# power_supply.net
KiCad netlist of a schematic drawn in Altium Designer
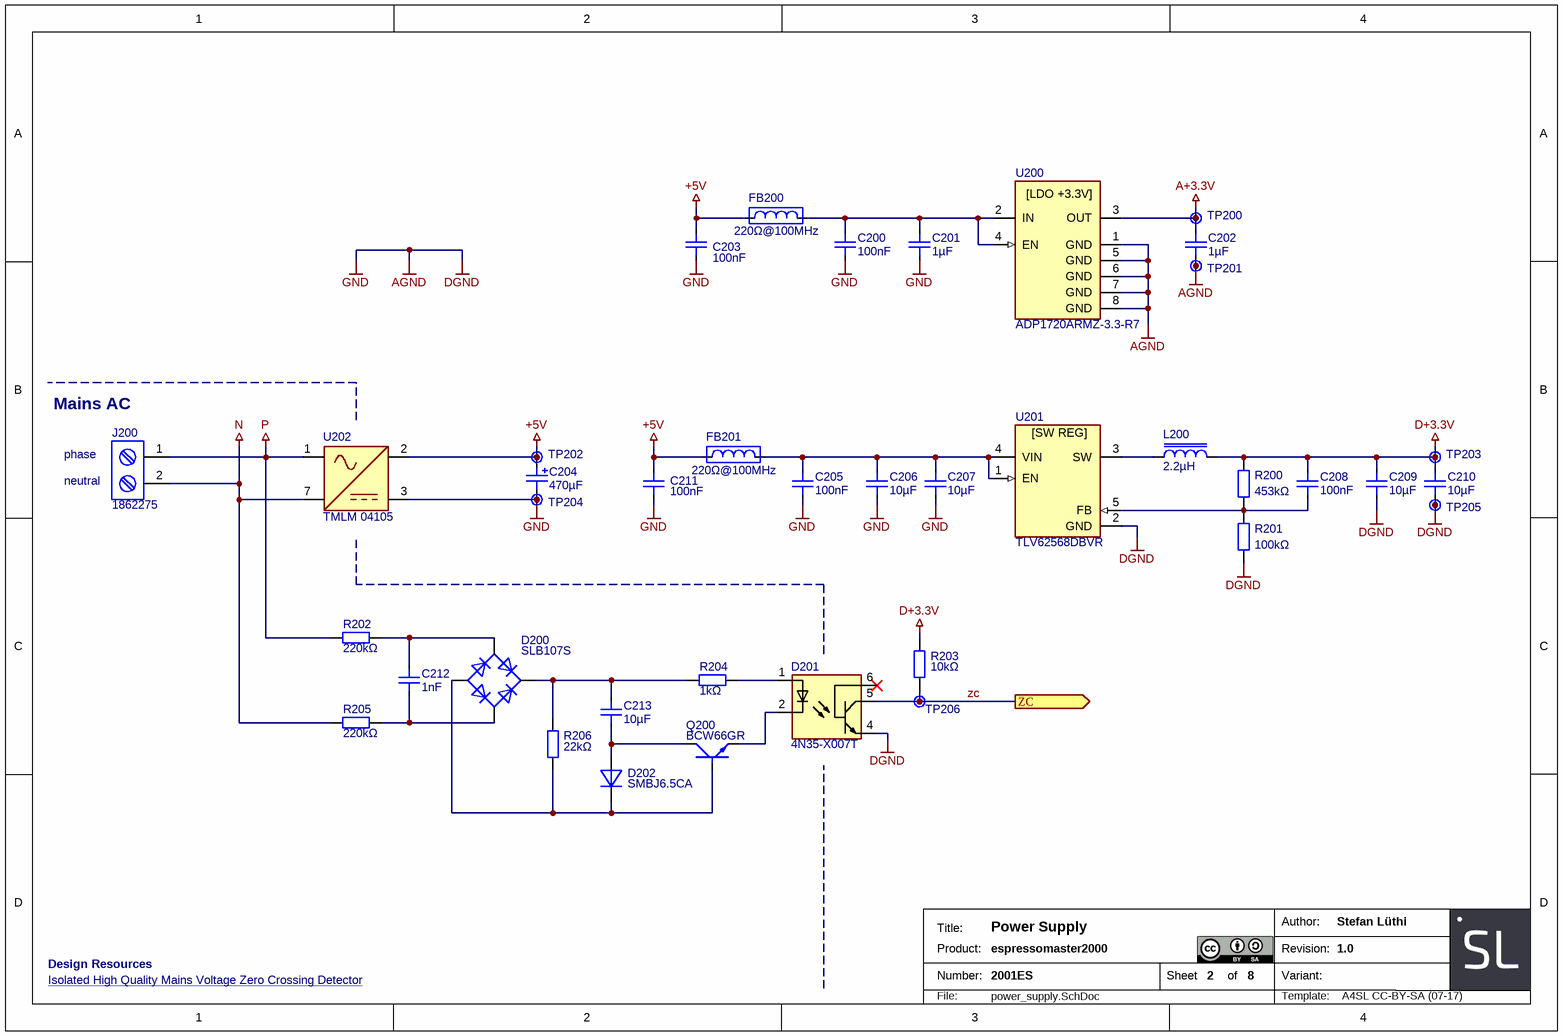
[diagram p0: power_supply.SchDoc]

(export (version "E")
  (design (tool "Eeschema 10.0.6"))
  (components
    (comp (ref "C200")
      (value "100nF")
      (footprint "SMD0603CAP")
      (description "Ceramic Capacitor")
      (libsource (lib "SL-Library") (part "Capacitor Ceramic"))
    )
    (comp (ref "C201")
      (value "1µF")
      (footprint "SMD0603CAP")
      (description "Ceramic Capacitor")
      (libsource (lib "SL-Library") (part "Capacitor Ceramic"))
    )
    (comp (ref "C202")
      (value "1µF")
      (footprint "SMD0603CAP")
      (description "Ceramic Capacitor")
      (libsource (lib "SL-Library") (part "Capacitor Ceramic"))
    )
    (comp (ref "C203")
      (value "100nF")
      (footprint "SMD0603CAP")
      (description "Ceramic Capacitor")
      (libsource (lib "SL-Library") (part "Capacitor Ceramic"))
    )
    (comp (ref "C204")
      (value "470µF")
      (footprint "CAP-12.5-20-5")
      (description "Elektrolytic Capacitor")
      (libsource (lib "SL-Library") (part "Capacitor Electrolytic"))
    )
    (comp (ref "C205")
      (value "100nF")
      (footprint "SMD0603CAP")
      (description "Ceramic Capacitor")
      (libsource (lib "SL-Library") (part "Capacitor Ceramic"))
    )
    (comp (ref "C206")
      (value "10µF")
      (footprint "SMD1206CAP")
      (description "Ceramic Capacitor")
      (libsource (lib "SL-Library") (part "Capacitor Ceramic"))
    )
    (comp (ref "C207")
      (value "10µF")
      (footprint "SMD1206CAP")
      (description "Ceramic Capacitor")
      (libsource (lib "SL-Library") (part "Capacitor Ceramic"))
    )
    (comp (ref "C208")
      (value "100nF")
      (footprint "SMD0603CAP")
      (description "Ceramic Capacitor")
      (libsource (lib "SL-Library") (part "Capacitor Ceramic"))
    )
    (comp (ref "C209")
      (value "10µF")
      (footprint "SMD1206CAP")
      (description "Ceramic Capacitor")
      (libsource (lib "SL-Library") (part "Capacitor Ceramic"))
    )
    (comp (ref "C210")
      (value "10µF")
      (footprint "SMD1206CAP")
      (description "Ceramic Capacitor")
      (libsource (lib "SL-Library") (part "Capacitor Ceramic"))
    )
    (comp (ref "C211")
      (value "100nF")
      (footprint "SMD0603CAP")
      (description "Ceramic Capacitor")
      (libsource (lib "SL-Library") (part "Capacitor Ceramic"))
    )
    (comp (ref "C212")
      (value "1nF")
      (footprint "SMD0603CAP")
      (description "Ceramic Capacitor")
      (libsource (lib "SL-Library") (part "Capacitor Ceramic"))
    )
    (comp (ref "C213")
      (value "10µF")
      (footprint "SMD1206CAP")
      (description "Ceramic Capacitor")
      (libsource (lib "SL-Library") (part "Capacitor Ceramic"))
    )
    (comp (ref "D200")
      (value "SLB107S")
      (footprint "SLDBS-4")
      (description "Full Bridge Rectifier")
      (libsource (lib "SL-Library") (part "Rectifier"))
    )
    (comp (ref "D201")
      (value "4N35-X007T")
      (footprint "SMT6-LB")
      (description "Optocoupler")
      (libsource (lib "SL-Library") (part "4N35-X"))
    )
    (comp (ref "D202")
      (value "SMBJ6.5CA")
      (footprint "DO-214AA")
      (description "Diode")
      (libsource (lib "SL-Library") (part "Diode"))
    )
    (comp (ref "FB200")
      (value "220Ω@100MHz")
      (footprint "SMD0603RES")
      (description "Ferrite Bead")
      (libsource (lib "SL-Library") (part "Ferrite Bead"))
    )
    (comp (ref "FB201")
      (value "220Ω@100MHz")
      (footprint "SMD0603RES")
      (description "Ferrite Bead")
      (libsource (lib "SL-Library") (part "Ferrite Bead"))
    )
    (comp (ref "J200")
      (value "1862275")
      (footprint "1862275")
      (description "Screw Terminal, 2 Position, 5mm Spacing")
      (libsource (lib "SL-Library") (part "1862275"))
    )
    (comp (ref "L200")
      (value "2.2µH")
      (footprint "WE4040")
      (description "Inductor")
      (libsource (lib "SL-Library") (part "Inductor"))
    )
    (comp (ref "Q200")
      (value "BCW66GR")
      (footprint "SOT-23")
      (description "Bipolar transistor NPN")
      (libsource (lib "SL-Library") (part "Transistor NPN"))
    )
    (comp (ref "R200")
      (value "453kΩ")
      (footprint "SMD0603RES")
      (description "Resistor")
      (libsource (lib "SL-Library") (part "Resistor"))
    )
    (comp (ref "R201")
      (value "100kΩ")
      (footprint "SMD0603RES")
      (description "Resistor")
      (libsource (lib "SL-Library") (part "Resistor"))
    )
    (comp (ref "R202")
      (value "220kΩ")
      (footprint "SMD2010RES")
      (description "Resistor")
      (libsource (lib "") (part "Resistor_1"))
    )
    (comp (ref "R203")
      (value "10kΩ")
      (footprint "SMD0603RES")
      (description "Resistor")
      (libsource (lib "SL-Library") (part "Resistor"))
    )
    (comp (ref "R204")
      (value "1kΩ")
      (footprint "SMD0603RES")
      (description "Resistor")
      (libsource (lib "") (part "Resistor_1"))
    )
    (comp (ref "R205")
      (value "220kΩ")
      (footprint "SMD2010RES")
      (description "Resistor")
      (libsource (lib "") (part "Resistor_1"))
    )
    (comp (ref "R206")
      (value "22kΩ")
      (footprint "SMD0603RES")
      (description "Resistor")
      (libsource (lib "SL-Library") (part "Resistor"))
    )
    (comp (ref "TP200")
      (value "Testpoint")
      (footprint "TP")
      (libsource (lib "SL-Library") (part "Testpoint"))
    )
    (comp (ref "TP201")
      (value "Testpoint")
      (footprint "TP")
      (libsource (lib "SL-Library") (part "Testpoint"))
    )
    (comp (ref "TP202")
      (value "Testpoint")
      (footprint "TP")
      (libsource (lib "SL-Library") (part "Testpoint"))
    )
    (comp (ref "TP203")
      (value "Testpoint")
      (footprint "TP")
      (libsource (lib "SL-Library") (part "Testpoint"))
    )
    (comp (ref "TP204")
      (value "Testpoint")
      (footprint "TP")
      (libsource (lib "SL-Library") (part "Testpoint"))
    )
    (comp (ref "TP205")
      (value "Testpoint")
      (footprint "TP")
      (libsource (lib "SL-Library") (part "Testpoint"))
    )
    (comp (ref "TP206")
      (value "Testpoint")
      (footprint "TP")
      (libsource (lib "SL-Library") (part "Testpoint"))
    )
    (comp (ref "U200")
      (value "ADP1720ARMZ-3.3-R7")
      (footprint "MSOP8")
      (description "LDO 3.3V Output")
      (libsource (lib "SL-Library") (part "ADP1720ARMZ-3.3-R7"))
    )
    (comp (ref "U201")
      (value "TLV62568DBVR")
      (footprint "SOT-23-5")
      (description "Step-Down Regulator")
      (libsource (lib "SL-Library") (part "TLV62568DBVR"))
    )
    (comp (ref "U202")
      (value "TMLM 04105")
      (footprint "TMLM04")
      (description "AC/DC Converter (100VAC - 240VAC to 5VDC)")
      (libsource (lib "SL-Library") (part "TMLM 04"))
    )
  )
  (nets
    (net (code "1") (name "+5V") (class "Default")
      (node (ref "C203") (pin "1") (pinfunction "1_1") (pintype "passive"))
      (node (ref "C204") (pin "P") (pinfunction "P_P") (pintype "passive"))
      (node (ref "C211") (pin "1") (pinfunction "1_1") (pintype "passive"))
      (node (ref "FB200") (pin "1") (pinfunction "1_1") (pintype "passive"))
      (node (ref "FB201") (pin "1") (pinfunction "1_1") (pintype "passive"))
      (node (ref "TP202") (pin "1") (pinfunction "1_1") (pintype "passive"))
      (node (ref "U202") (pin "2") (pinfunction "V+_2") (pintype "power_in"))
    )
    (net (code "2") (name "/zc") (class "Default")
      (node (ref "D201") (pin "5") (pinfunction "5_5") (pintype "passive"))
      (node (ref "R203") (pin "1") (pinfunction "1_1") (pintype "passive"))
      (node (ref "TP206") (pin "1") (pinfunction "1_1") (pintype "passive"))
    )
    (net (code "3") (name "A+3.3V") (class "Default")
      (node (ref "C202") (pin "1") (pinfunction "1_1") (pintype "passive"))
      (node (ref "TP200") (pin "1") (pinfunction "1_1") (pintype "passive"))
      (node (ref "U200") (pin "3") (pinfunction "OUT_3") (pintype "power_in"))
    )
    (net (code "4") (name "AGND") (class "Default")
      (node (ref "C200") (pin "2") (pinfunction "2_2") (pintype "passive"))
      (node (ref "C201") (pin "2") (pinfunction "2_2") (pintype "passive"))
      (node (ref "C202") (pin "2") (pinfunction "2_2") (pintype "passive"))
      (node (ref "C203") (pin "2") (pinfunction "2_2") (pintype "passive"))
      (node (ref "C204") (pin "M") (pinfunction "M_M") (pintype "passive"))
      (node (ref "C205") (pin "2") (pinfunction "2_2") (pintype "passive"))
      (node (ref "C206") (pin "2") (pinfunction "2_2") (pintype "passive"))
      (node (ref "C207") (pin "2") (pinfunction "2_2") (pintype "passive"))
      (node (ref "C209") (pin "2") (pinfunction "2_2") (pintype "passive"))
      (node (ref "C210") (pin "2") (pinfunction "2_2") (pintype "passive"))
      (node (ref "C211") (pin "2") (pinfunction "2_2") (pintype "passive"))
      (node (ref "D201") (pin "4") (pinfunction "4_4") (pintype "passive"))
      (node (ref "R201") (pin "1") (pinfunction "1_1") (pintype "passive"))
      (node (ref "TP201") (pin "1") (pinfunction "1_1") (pintype "passive"))
      (node (ref "TP204") (pin "1") (pinfunction "1_1") (pintype "passive"))
      (node (ref "TP205") (pin "1") (pinfunction "1_1") (pintype "passive"))
      (node (ref "U200") (pin "1") (pinfunction "GND_1") (pintype "power_in"))
      (node (ref "U200") (pin "5") (pinfunction "GND_5") (pintype "power_in"))
      (node (ref "U200") (pin "6") (pinfunction "GND_6") (pintype "power_in"))
      (node (ref "U200") (pin "7") (pinfunction "GND_7") (pintype "power_in"))
      (node (ref "U200") (pin "8") (pinfunction "GND_8") (pintype "power_in"))
      (node (ref "U201") (pin "2") (pinfunction "GND_2") (pintype "power_in"))
      (node (ref "U202") (pin "3") (pinfunction "GND_3") (pintype "power_in"))
    )
    (net (code "5") (name "D+3.3V") (class "Default")
      (node (ref "C208") (pin "1") (pinfunction "1_1") (pintype "passive"))
      (node (ref "C209") (pin "1") (pinfunction "1_1") (pintype "passive"))
      (node (ref "C210") (pin "1") (pinfunction "1_1") (pintype "passive"))
      (node (ref "L200") (pin "2") (pinfunction "2_2") (pintype "passive"))
      (node (ref "R200") (pin "2") (pinfunction "2_2") (pintype "passive"))
      (node (ref "R203") (pin "2") (pinfunction "2_2") (pintype "passive"))
      (node (ref "TP203") (pin "1") (pinfunction "1_1") (pintype "passive"))
    )
    (net (code "6") (name "N") (class "Default")
      (node (ref "J200") (pin "2") (pinfunction "2_2") (pintype "passive"))
      (node (ref "R205") (pin "2") (pinfunction "2_2") (pintype "passive"))
      (node (ref "U202") (pin "7") (pinfunction "AC_7") (pintype "power_in"))
    )
    (net (code "7") (name "Net-(C212-Pad1)") (class "Default")
      (node (ref "C212") (pin "1") (pinfunction "1_1") (pintype "passive"))
      (node (ref "D200") (pin "3") (pinfunction "3_3") (pintype "passive"))
      (node (ref "R205") (pin "1") (pinfunction "1_1") (pintype "passive"))
    )
    (net (code "8") (name "Net-(C212-Pad2)") (class "Default")
      (node (ref "C212") (pin "2") (pinfunction "2_2") (pintype "passive"))
      (node (ref "D200") (pin "2") (pinfunction "2_2") (pintype "passive"))
      (node (ref "R202") (pin "1") (pinfunction "1_1") (pintype "passive"))
    )
    (net (code "9") (name "Net-(C213-Pad1)") (class "Default")
      (node (ref "C213") (pin "1") (pinfunction "1_1") (pintype "passive"))
      (node (ref "D200") (pin "1") (pinfunction "1_1") (pintype "passive"))
      (node (ref "R204") (pin "2") (pinfunction "2_2") (pintype "passive"))
      (node (ref "R206") (pin "2") (pinfunction "2_2") (pintype "passive"))
    )
    (net (code "10") (name "Net-(D201-Pad1)") (class "Default")
      (node (ref "D201") (pin "1") (pinfunction "1_1") (pintype "passive"))
      (node (ref "R204") (pin "1") (pinfunction "1_1") (pintype "passive"))
    )
    (net (code "11") (name "Net-(Q200-B)") (class "Default")
      (node (ref "D200") (pin "4") (pinfunction "4_4") (pintype "passive"))
      (node (ref "D202") (pin "C") (pinfunction "C_C") (pintype "passive"))
      (node (ref "Q200") (pin "1") (pinfunction "B_1") (pintype "passive"))
      (node (ref "R206") (pin "1") (pinfunction "1_1") (pintype "passive"))
    )
    (net (code "12") (name "Net-(Q200-C)") (class "Default")
      (node (ref "C213") (pin "2") (pinfunction "2_2") (pintype "passive"))
      (node (ref "D202") (pin "A") (pinfunction "A_A") (pintype "passive"))
      (node (ref "Q200") (pin "3") (pinfunction "C_3") (pintype "passive"))
    )
    (net (code "13") (name "Net-(Q200-E)") (class "Default")
      (node (ref "D201") (pin "2") (pinfunction "2_2") (pintype "passive"))
      (node (ref "Q200") (pin "2") (pinfunction "E_2") (pintype "passive"))
    )
    (net (code "14") (name "Net-(U200-EN)") (class "Default")
      (node (ref "C200") (pin "1") (pinfunction "1_1") (pintype "passive"))
      (node (ref "C201") (pin "1") (pinfunction "1_1") (pintype "passive"))
      (node (ref "FB200") (pin "2") (pinfunction "2_2") (pintype "passive"))
      (node (ref "U200") (pin "2") (pinfunction "IN_2") (pintype "power_in"))
      (node (ref "U200") (pin "4") (pinfunction "EN_4") (pintype "input"))
    )
    (net (code "15") (name "Net-(U201-EN)") (class "Default")
      (node (ref "C205") (pin "1") (pinfunction "1_1") (pintype "passive"))
      (node (ref "C206") (pin "1") (pinfunction "1_1") (pintype "passive"))
      (node (ref "C207") (pin "1") (pinfunction "1_1") (pintype "passive"))
      (node (ref "FB201") (pin "2") (pinfunction "2_2") (pintype "passive"))
      (node (ref "U201") (pin "1") (pinfunction "EN_1") (pintype "input"))
      (node (ref "U201") (pin "4") (pinfunction "VIN_4") (pintype "power_in"))
    )
    (net (code "16") (name "Net-(U201-FB)") (class "Default")
      (node (ref "C208") (pin "2") (pinfunction "2_2") (pintype "passive"))
      (node (ref "R200") (pin "1") (pinfunction "1_1") (pintype "passive"))
      (node (ref "R201") (pin "2") (pinfunction "2_2") (pintype "passive"))
      (node (ref "U201") (pin "5") (pinfunction "FB_5") (pintype "input"))
    )
    (net (code "17") (name "Net-(U201-SW)") (class "Default")
      (node (ref "L200") (pin "1") (pinfunction "1_1") (pintype "passive"))
      (node (ref "U201") (pin "3") (pinfunction "SW_3") (pintype "power_in"))
    )
    (net (code "18") (name "P") (class "Default")
      (node (ref "J200") (pin "1") (pinfunction "1_1") (pintype "passive"))
      (node (ref "R202") (pin "2") (pinfunction "2_2") (pintype "passive"))
      (node (ref "U202") (pin "1") (pinfunction "AC_1") (pintype "power_in"))
    )
    (net (code "19") (name "unconnected-(D201-Pad6)") (class "Default")
      (node (ref "D201") (pin "6") (pinfunction "6_6") (pintype "passive+no_connect"))
    )
  )
)
